# Sheet1.net
KiCad netlist of a schematic drawn in Altium Designer
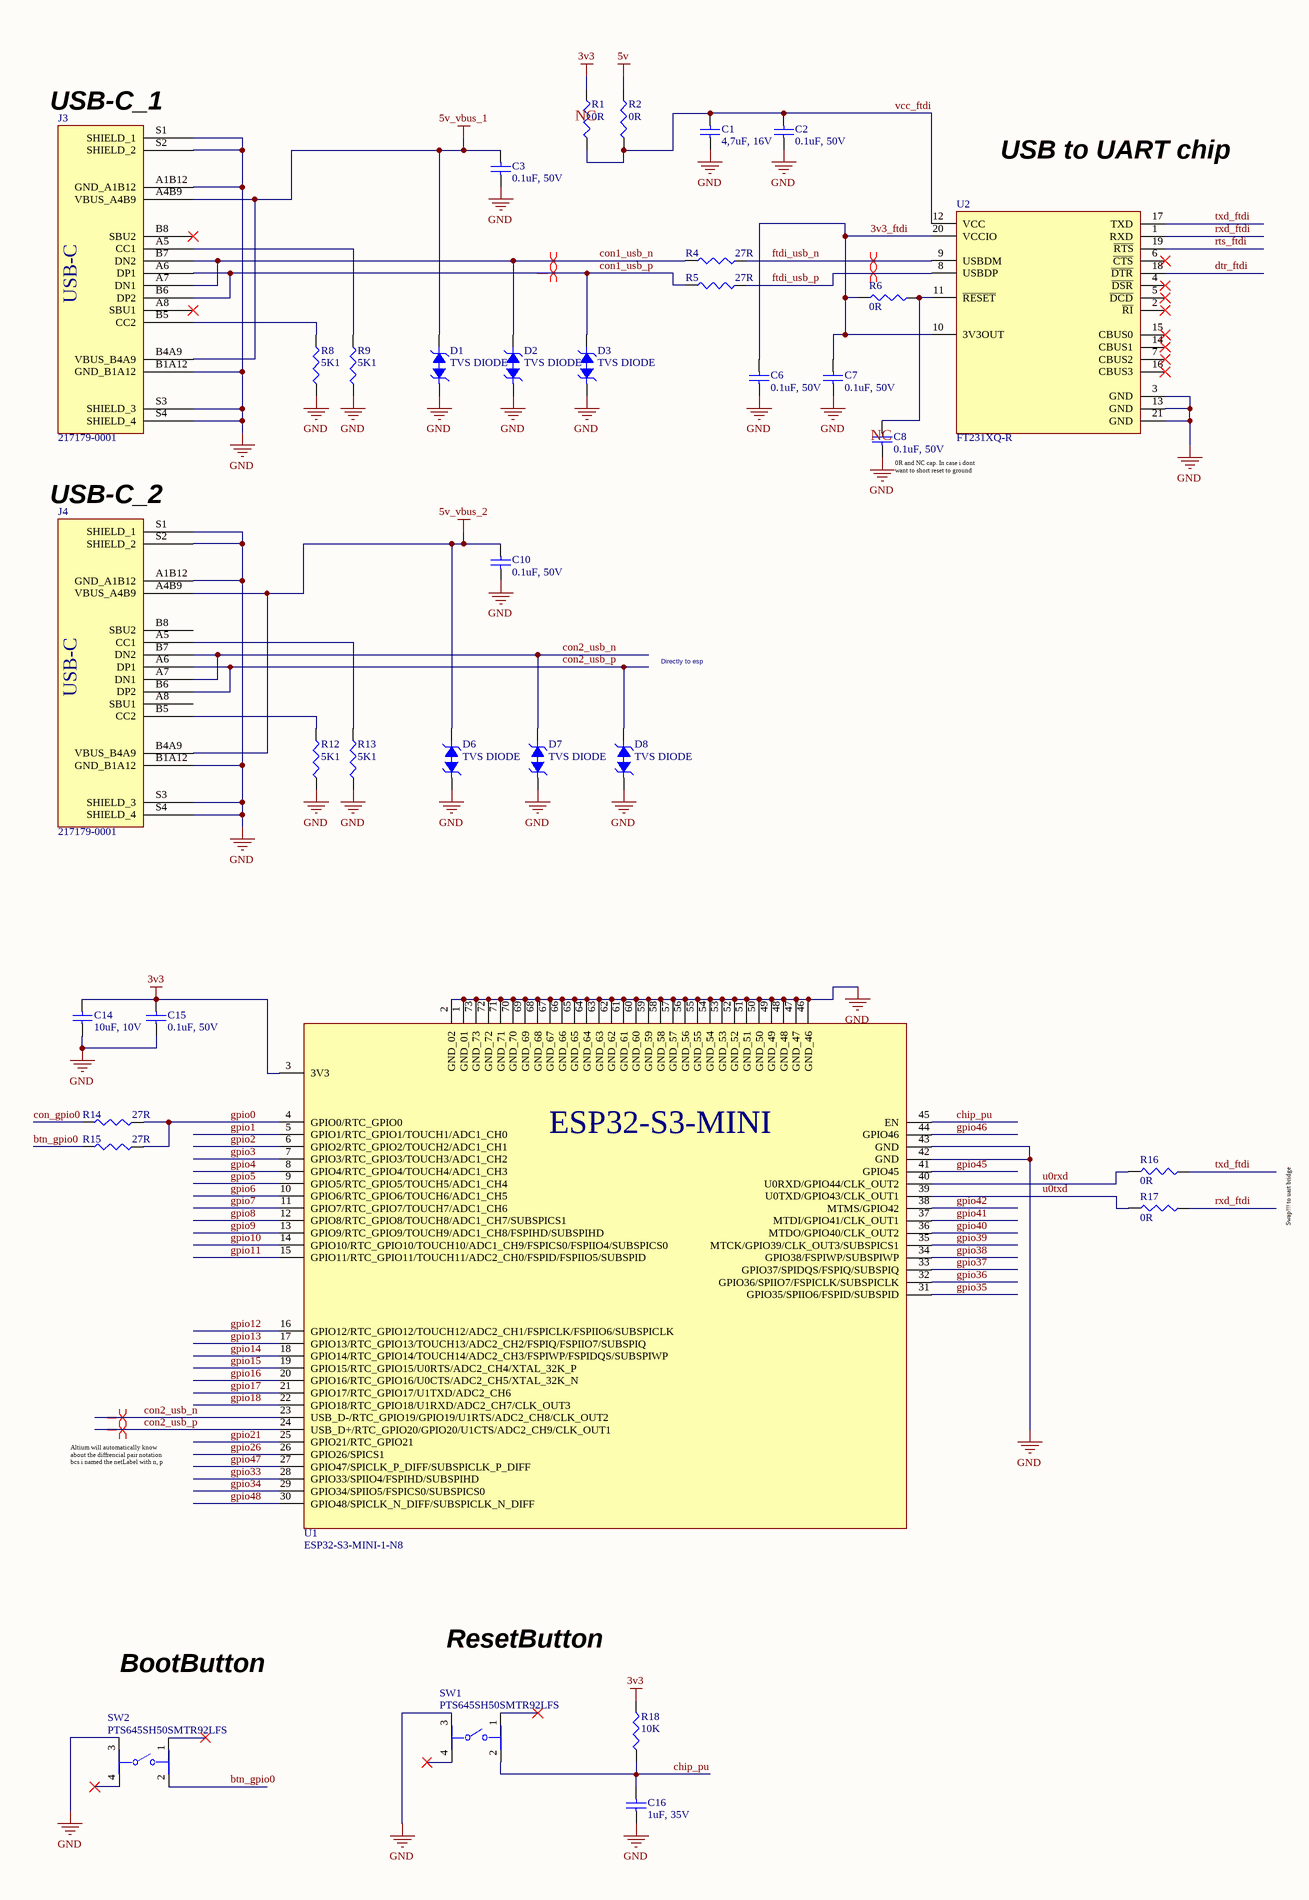
[diagram p0: Sheet1.SchDoc, left]
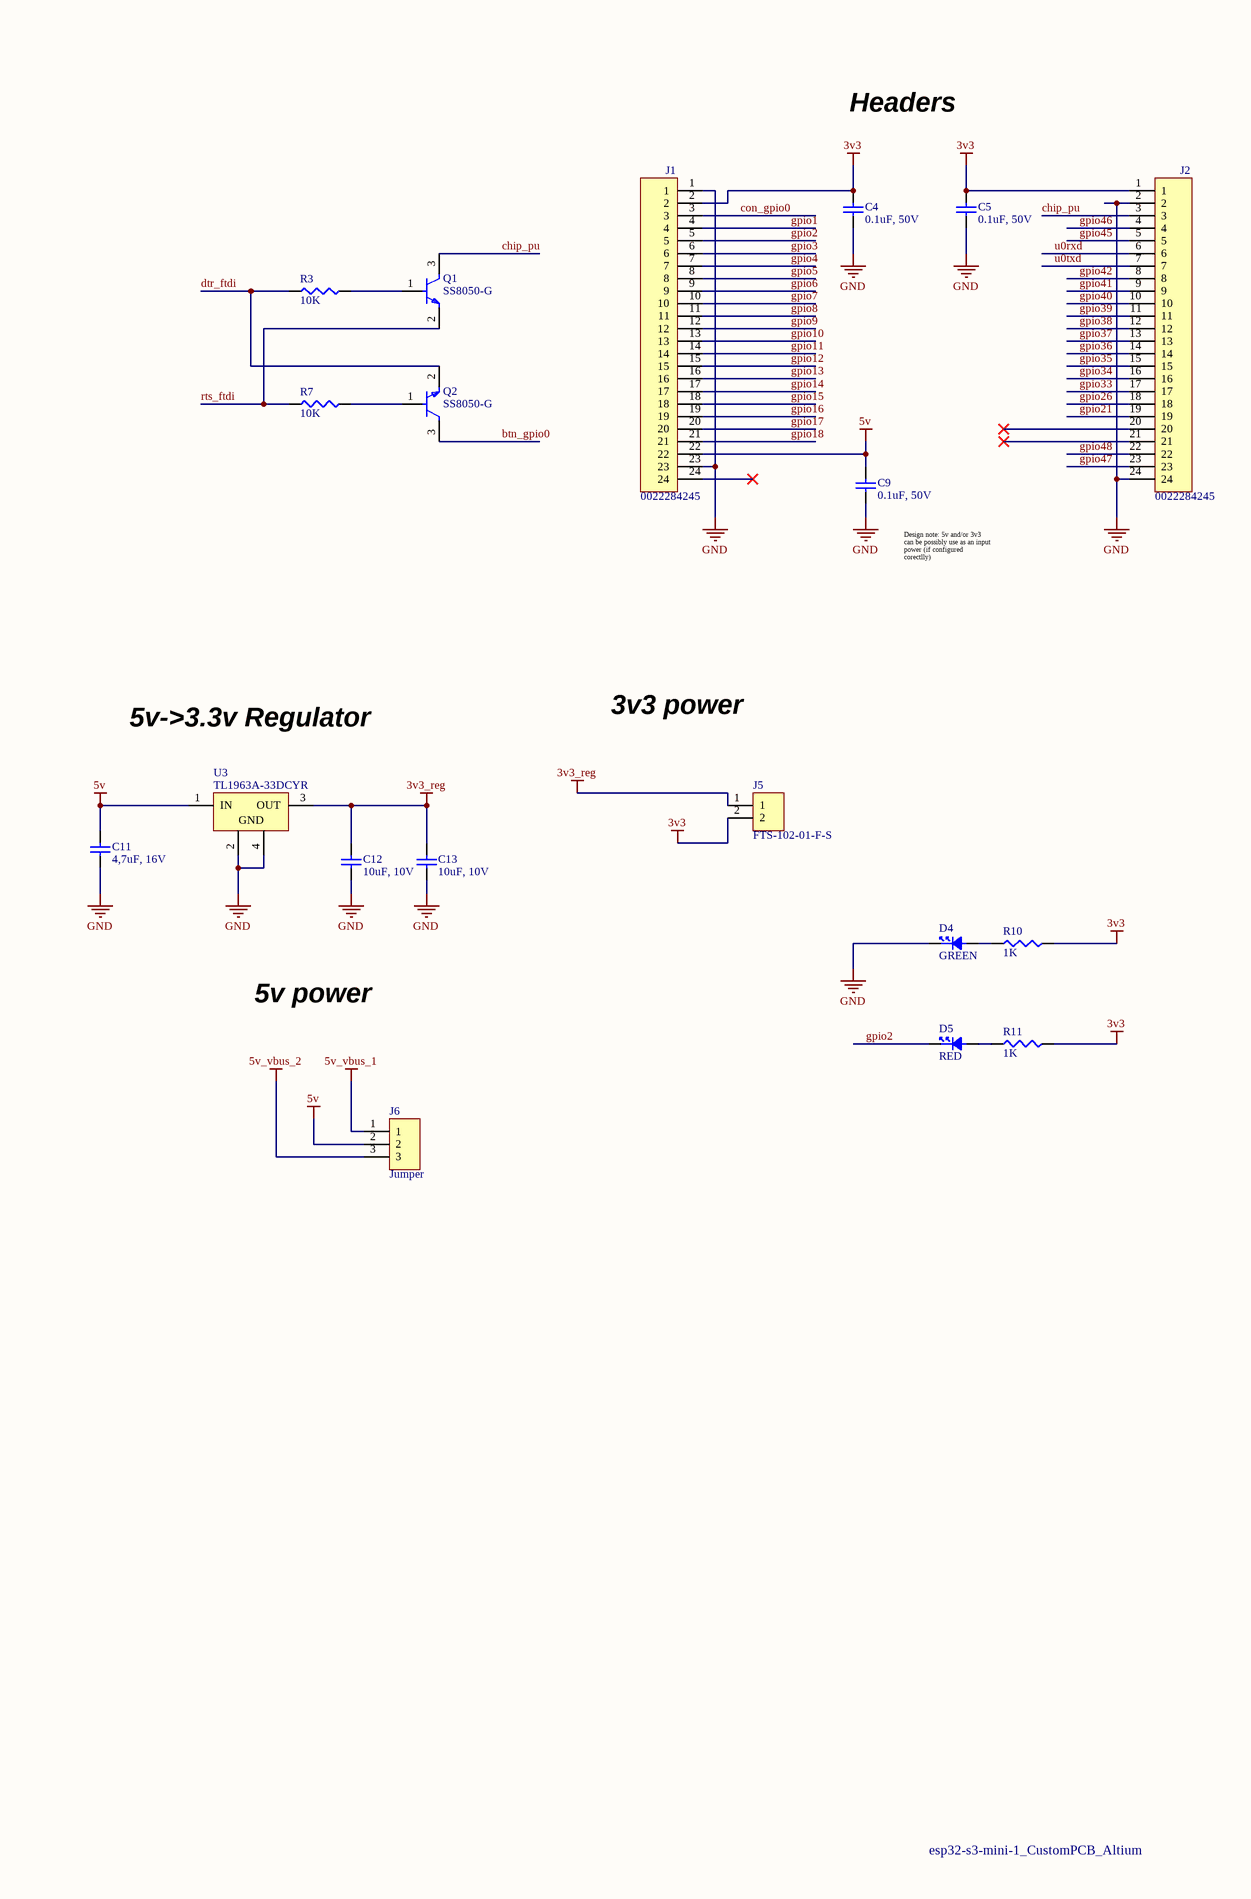
[diagram p1: Sheet1.SchDoc, right]

(export (version "E")
  (design (tool "Eeschema 10.0.6"))
  (components
    (comp (ref "C1")
      (value "4,7uF, 16V")
      (footprint "CAPC1005X55N")
      (description "CAP CER 4.7UF 16V X5R 0402")
      (fields
        (field (name "MANUFACTURER") "Samsung")
        (field (name "MANUFACTURER PART NUMBER") "CL05A475MO5NUNC")
      )
      (libsource (lib "Schlib1") (part "CL05A475MO5NUNC"))
    )
    (comp (ref "C2")
      (value "0.1uF, 50V")
      (footprint "CAPC1005X55N")
      (description "CAP CER 0.1UF 50V X7R 0402")
      (fields
        (field (name "MANUFACTURER") "Samsung")
        (field (name "MANUFACTURER PART NUMBER") "CL05B104KB54PNC")
      )
      (libsource (lib "Schlib1") (part "CL05B104KB54PNC"))
    )
    (comp (ref "C3")
      (value "0.1uF, 50V")
      (footprint "CAPC1005X55N")
      (description "CAP CER 0.1UF 50V X7R 0402")
      (fields
        (field (name "MANUFACTURER") "Samsung")
        (field (name "MANUFACTURER PART NUMBER") "CL05B104KB54PNC")
      )
      (libsource (lib "Schlib1") (part "CL05B104KB54PNC"))
    )
    (comp (ref "C4")
      (value "0.1uF, 50V")
      (footprint "CAPC1005X55N")
      (description "CAP CER 0.1UF 50V X7R 0402")
      (fields
        (field (name "MANUFACTURER") "Samsung")
        (field (name "MANUFACTURER PART NUMBER") "CL05B104KB54PNC")
      )
      (libsource (lib "Schlib1") (part "CL05B104KB54PNC"))
    )
    (comp (ref "C5")
      (value "0.1uF, 50V")
      (footprint "CAPC1005X55N")
      (description "CAP CER 0.1UF 50V X7R 0402")
      (fields
        (field (name "MANUFACTURER") "Samsung")
        (field (name "MANUFACTURER PART NUMBER") "CL05B104KB54PNC")
      )
      (libsource (lib "Schlib1") (part "CL05B104KB54PNC"))
    )
    (comp (ref "C6")
      (value "0.1uF, 50V")
      (footprint "CAPC1005X55N")
      (description "CAP CER 0.1UF 50V X7R 0402")
      (fields
        (field (name "MANUFACTURER") "Samsung")
        (field (name "MANUFACTURER PART NUMBER") "CL05B104KB54PNC")
      )
      (libsource (lib "Schlib1") (part "CL05B104KB54PNC"))
    )
    (comp (ref "C7")
      (value "0.1uF, 50V")
      (footprint "CAPC1005X55N")
      (description "CAP CER 0.1UF 50V X7R 0402")
      (fields
        (field (name "MANUFACTURER") "Samsung")
        (field (name "MANUFACTURER PART NUMBER") "CL05B104KB54PNC")
      )
      (libsource (lib "Schlib1") (part "CL05B104KB54PNC"))
    )
    (comp (ref "C8")
      (value "0.1uF, 50V")
      (footprint "CAPC1005X55N")
      (description "CAP CER 0.1UF 50V X7R 0402")
      (fields
        (field (name "MANUFACTURER") "Samsung")
        (field (name "MANUFACTURER PART NUMBER") "CL05B104KB54PNC")
      )
      (libsource (lib "Schlib1") (part "CL05B104KB54PNC"))
    )
    (comp (ref "C9")
      (value "0.1uF, 50V")
      (footprint "CAPC1005X55N")
      (description "CAP CER 0.1UF 50V X7R 0402")
      (fields
        (field (name "MANUFACTURER") "Samsung")
        (field (name "MANUFACTURER PART NUMBER") "CL05B104KB54PNC")
      )
      (libsource (lib "Schlib1") (part "CL05B104KB54PNC"))
    )
    (comp (ref "C10")
      (value "0.1uF, 50V")
      (footprint "CAPC1005X55N")
      (description "CAP CER 0.1UF 50V X7R 0402")
      (fields
        (field (name "MANUFACTURER") "Samsung")
        (field (name "MANUFACTURER PART NUMBER") "CL05B104KB54PNC")
      )
      (libsource (lib "Schlib1") (part "CL05B104KB54PNC"))
    )
    (comp (ref "C11")
      (value "4,7uF, 16V")
      (footprint "CAPC1005X55N")
      (description "CAP CER 4.7UF 16V X5R 0402")
      (fields
        (field (name "MANUFACTURER") "Samsung")
        (field (name "MANUFACTURER PART NUMBER") "CL05A475MO5NUNC")
      )
      (libsource (lib "Schlib1") (part "CL05A475MO5NUNC"))
    )
    (comp (ref "C12")
      (value "10uF, 10V")
      (footprint "CAPC1005X55N")
      (description "CAP CER 10UF 10V X5R 0402")
      (fields
        (field (name "MANUFACTURER") "Samsung")
        (field (name "MANUFACTURER PART NUMBER") "CL05A106MP8NUB8")
      )
      (libsource (lib "Schlib1") (part "CL05A106MP8NUB8"))
    )
    (comp (ref "C13")
      (value "10uF, 10V")
      (footprint "CAPC1005X55N")
      (description "CAP CER 10UF 10V X5R 0402")
      (fields
        (field (name "MANUFACTURER") "Samsung")
        (field (name "MANUFACTURER PART NUMBER") "CL05A106MP8NUB8")
      )
      (libsource (lib "Schlib1") (part "CL05A106MP8NUB8"))
    )
    (comp (ref "C14")
      (value "10uF, 10V")
      (footprint "CAPC1005X55N")
      (description "CAP CER 10UF 10V X5R 0402")
      (fields
        (field (name "MANUFACTURER") "Samsung")
        (field (name "MANUFACTURER PART NUMBER") "CL05A106MP8NUB8")
      )
      (libsource (lib "Schlib1") (part "CL05A106MP8NUB8"))
    )
    (comp (ref "C15")
      (value "0.1uF, 50V")
      (footprint "CAPC1005X55N")
      (description "CAP CER 0.1UF 50V X7R 0402")
      (fields
        (field (name "MANUFACTURER") "Samsung")
        (field (name "MANUFACTURER PART NUMBER") "CL05B104KB54PNC")
      )
      (libsource (lib "Schlib1") (part "CL05B104KB54PNC"))
    )
    (comp (ref "C16")
      (value "1uF, 35V")
      (footprint "CAPC1005X55N")
      (description "CAP CER 1UF 35V X5R 0402")
      (fields
        (field (name "MANUFACTURER") "Samsung")
        (field (name "MANUFACTURER PART NUMBER") "CL05A105KL5NRNC")
      )
      (libsource (lib "Schlib1") (part "CL05A105KL5NRNC"))
    )
    (comp (ref "D1")
      (value "TVS DIODE")
      (footprint "tvsDiode")
      (description "TVS DIODE 5.3VWM 12VC SOD882 - AQ3045-01ETG")
      (fields
        (field (name "MANUFACTURER") "Littelfuse")
        (field (name "MANUFACTURER PART NUMBER") "AQ3045-01ETG")
      )
      (libsource (lib "Schlib1") (part "TVS DIODE"))
    )
    (comp (ref "D2")
      (value "TVS DIODE")
      (footprint "tvsDiode")
      (description "TVS DIODE 5.3VWM 12VC SOD882 - AQ3045-01ETG")
      (fields
        (field (name "MANUFACTURER") "Littelfuse")
        (field (name "MANUFACTURER PART NUMBER") "AQ3045-01ETG")
      )
      (libsource (lib "Schlib1") (part "TVS DIODE"))
    )
    (comp (ref "D3")
      (value "TVS DIODE")
      (footprint "tvsDiode")
      (description "TVS DIODE 5.3VWM 12VC SOD882 - AQ3045-01ETG")
      (fields
        (field (name "MANUFACTURER") "Littelfuse")
        (field (name "MANUFACTURER PART NUMBER") "AQ3045-01ETG")
      )
      (libsource (lib "Schlib1") (part "TVS DIODE"))
    )
    (comp (ref "D4")
      (value "GREEN")
      (footprint "LED0402G")
      (description "LED YLW-GRN 0402 SMD")
      (fields
        (field (name "MANUFACTURER") "Vishay")
        (field (name "MANUFACTURER PART NUMBER") "VLMG1500-GS08")
      )
      (libsource (lib "Schlib1") (part "VLMG1500-GS08"))
    )
    (comp (ref "D5")
      (value "RED")
      (footprint "LED0402R")
      (description "LED RED 0402 SMD")
      (fields
        (field (name "MANUFACTURER") "Vishay")
        (field (name "MANUFACTURER PART NUMBER") "VLMS1500-GS08")
      )
      (libsource (lib "Schlib1") (part "VLMS1500-GS08"))
    )
    (comp (ref "D6")
      (value "TVS DIODE")
      (footprint "tvsDiode")
      (description "TVS DIODE 5.3VWM 12VC SOD882 - AQ3045-01ETG")
      (fields
        (field (name "MANUFACTURER") "Littelfuse")
        (field (name "MANUFACTURER PART NUMBER") "AQ3045-01ETG")
      )
      (libsource (lib "Schlib1") (part "TVS DIODE"))
    )
    (comp (ref "D7")
      (value "TVS DIODE")
      (footprint "tvsDiode")
      (description "TVS DIODE 5.3VWM 12VC SOD882 - AQ3045-01ETG")
      (fields
        (field (name "MANUFACTURER") "Littelfuse")
        (field (name "MANUFACTURER PART NUMBER") "AQ3045-01ETG")
      )
      (libsource (lib "Schlib1") (part "TVS DIODE"))
    )
    (comp (ref "D8")
      (value "TVS DIODE")
      (footprint "tvsDiode")
      (description "TVS DIODE 5.3VWM 12VC SOD882 - AQ3045-01ETG")
      (fields
        (field (name "MANUFACTURER") "Littelfuse")
        (field (name "MANUFACTURER PART NUMBER") "AQ3045-01ETG")
      )
      (libsource (lib "Schlib1") (part "TVS DIODE"))
    )
    (comp (ref "J1")
      (value "0022284245")
      (footprint "Header_1x24")
      (description "CONN HEADER VERT 24POS 2.54MM")
      (fields (field (name "MANUFACTURER") "Molex") (field (name "LCSC PART NUMBER") "C7145888"))
      (libsource (lib "") (part "0022284245_1"))
    )
    (comp (ref "J2")
      (value "0022284245")
      (footprint "Header_1x24")
      (description "CONN HEADER VERT 24POS 2.54MM")
      (fields (field (name "MANUFACTURER") "Molex") (field (name "LCSC PART NUMBER") "C7145888"))
      (libsource (lib "Schlib1") (part "0022284245"))
    )
    (comp (ref "J3")
      (value "217179-0001")
      (footprint "FP-2171790001-MFG")
      (description "CONN RCP USB2.0 TYP C 24P SMD RA")
      (fields (field (name "MANUFACTURER") "Molex") (field (name "LCSC PART NUMBER") "C3197684"))
      (libsource (lib "Schlib1") (part "217179-0001"))
    )
    (comp (ref "J4")
      (value "217179-0001")
      (footprint "FP-2171790001-MFG")
      (description "CONN RCP USB2.0 TYP C 24P SMD RA")
      (fields (field (name "MANUFACTURER") "Molex") (field (name "LCSC PART NUMBER") "C3197684"))
      (libsource (lib "Schlib1") (part "217179-0001"))
    )
    (comp (ref "J5")
      (value "FTS-102-01-F-S")
      (footprint "Header_1X2")
      (description "CONN HEADER VERT 2POS 1.27MM")
      (fields (field (name "MANUFACTURER") "Samtec") (field (name "LCSC PART NUMBER") "C6045317"))
      (libsource (lib "Schlib1") (part "FTS-102-01-F-S"))
    )
    (comp (ref "J6")
      (value "Jumper")
      (footprint "Header_3x1")
      (description "CONN HEADER VERT 3POS 1.27MM")
      (fields
        (field (name "MANUFACTURER") "Samtec")
        (field (name "MANUFACTURER PART NUMBER") "FTS-103-01-F-S")
      )
      (libsource (lib "Schlib1") (part "FTS-103-01-F-S."))
    )
    (comp (ref "Q1")
      (value "SS8050-G")
      (footprint "FP-SS8050-G-IPC_B")
      (description "TRANS NPN 25V 1.5A SOT23-3")
      (fields (field (name "MANUFACTURER") "Comchip") (field (name "LCSC PART NUMBER") "C164886"))
      (libsource (lib "Schlib1") (part "SS8050-G"))
    )
    (comp (ref "Q2")
      (value "SS8050-G")
      (footprint "FP-SS8050-G-IPC_B")
      (description "TRANS NPN 25V 1.5A SOT23-3")
      (fields (field (name "MANUFACTURER") "Comchip") (field (name "LCSC PART NUMBER") "C164886"))
      (libsource (lib "Schlib1") (part "SS8050-G"))
    )
    (comp (ref "R1")
      (value "0R")
      (footprint "RESC1005X37N")
      (description "RES 0 OHM JUMPER 1/16W 0402")
      (fields
        (field (name "MANUFACTURER") "Yageo")
        (field (name "MANUFACTURER PART NUMBER") "RC0402JR-070RL")
      )
      (libsource (lib "Schlib1") (part "RC0402JR-070RL"))
    )
    (comp (ref "R2")
      (value "0R")
      (footprint "RESC1005X37N")
      (description "RES 0 OHM JUMPER 1/16W 0402")
      (fields
        (field (name "MANUFACTURER") "Yageo")
        (field (name "MANUFACTURER PART NUMBER") "RC0402JR-070RL")
      )
      (libsource (lib "Schlib1") (part "RC0402JR-070RL"))
    )
    (comp (ref "R3")
      (value "10K")
      (footprint "RESC1005X37N")
      (description "RES SMD 10K OHM 1% 1/16W 0402")
      (fields
        (field (name "MANUFACTURER") "Yageo")
        (field (name "MANUFACTURER PART NUMBER") "AC0402FR-0710KL")
      )
      (libsource (lib "Schlib1") (part "AC0402FR-0710KL"))
    )
    (comp (ref "R4")
      (value "27R")
      (footprint "RESC1005X37N")
      (description "RES 27 OHM 1% 1/16W 0402")
      (fields
        (field (name "MANUFACTURER") "Yageo")
        (field (name "MANUFACTURER PART NUMBER") "RC0402FR-0727RL")
      )
      (libsource (lib "Schlib1") (part "RC0402FR-0727RL"))
    )
    (comp (ref "R5")
      (value "27R")
      (footprint "RESC1005X37N")
      (description "RES 27 OHM 1% 1/16W 0402")
      (fields
        (field (name "MANUFACTURER") "Yageo")
        (field (name "MANUFACTURER PART NUMBER") "RC0402FR-0727RL")
      )
      (libsource (lib "Schlib1") (part "RC0402FR-0727RL"))
    )
    (comp (ref "R6")
      (value "0R")
      (footprint "RESC1005X37N")
      (description "RES 0 OHM JUMPER 1/16W 0402")
      (fields
        (field (name "MANUFACTURER") "Yageo")
        (field (name "MANUFACTURER PART NUMBER") "RC0402JR-070RL")
      )
      (libsource (lib "Schlib1") (part "RC0402JR-070RL"))
    )
    (comp (ref "R7")
      (value "10K")
      (footprint "RESC1005X37N")
      (description "RES SMD 10K OHM 1% 1/16W 0402")
      (fields
        (field (name "MANUFACTURER") "Yageo")
        (field (name "MANUFACTURER PART NUMBER") "AC0402FR-0710KL")
      )
      (libsource (lib "Schlib1") (part "AC0402FR-0710KL"))
    )
    (comp (ref "R8")
      (value "5K1")
      (footprint "RESC1005X37N")
      (description "RES SMD 5.1K OHM 1% 1/16W 0402")
      (fields
        (field (name "MANUFACTURER") "Yageo")
        (field (name "MANUFACTURER PART NUMBER") "AC0402FR-075K1L")
      )
      (libsource (lib "Schlib1") (part "AC0402FR-075K1L"))
    )
    (comp (ref "R9")
      (value "5K1")
      (footprint "RESC1005X37N")
      (description "RES SMD 5.1K OHM 1% 1/16W 0402")
      (fields
        (field (name "MANUFACTURER") "Yageo")
        (field (name "MANUFACTURER PART NUMBER") "AC0402FR-075K1L")
      )
      (libsource (lib "*") (part "AC0402FR-075K1L"))
    )
    (comp (ref "R10")
      (value "1K")
      (footprint "RESC1005X37N")
      (description "RES 1K OHM 1% 1/16W 0402")
      (fields
        (field (name "MANUFACTURER") "Yageo")
        (field (name "MANUFACTURER PART NUMBER") "RC0402FR-071KL")
      )
      (libsource (lib "Schlib1") (part "RC0402FR-071KL"))
    )
    (comp (ref "R11")
      (value "1K")
      (footprint "RESC1005X37N")
      (description "RES 1K OHM 1% 1/16W 0402")
      (fields
        (field (name "MANUFACTURER") "Yageo")
        (field (name "MANUFACTURER PART NUMBER") "RC0402FR-071KL")
      )
      (libsource (lib "Schlib1") (part "RC0402FR-071KL"))
    )
    (comp (ref "R12")
      (value "5K1")
      (footprint "RESC1005X37N")
      (description "RES SMD 5.1K OHM 1% 1/16W 0402")
      (fields
        (field (name "MANUFACTURER") "Yageo")
        (field (name "MANUFACTURER PART NUMBER") "AC0402FR-075K1L")
      )
      (libsource (lib "Schlib1") (part "AC0402FR-075K1L"))
    )
    (comp (ref "R13")
      (value "5K1")
      (footprint "RESC1005X37N")
      (description "RES SMD 5.1K OHM 1% 1/16W 0402")
      (fields
        (field (name "MANUFACTURER") "Yageo")
        (field (name "MANUFACTURER PART NUMBER") "AC0402FR-075K1L")
      )
      (libsource (lib "*") (part "AC0402FR-075K1L"))
    )
    (comp (ref "R14")
      (value "27R")
      (footprint "RESC1005X37N")
      (description "RES 27 OHM 1% 1/16W 0402")
      (fields
        (field (name "MANUFACTURER") "Yageo")
        (field (name "MANUFACTURER PART NUMBER") "RC0402FR-0727RL")
      )
      (libsource (lib "Schlib1") (part "RC0402FR-0727RL"))
    )
    (comp (ref "R15")
      (value "27R")
      (footprint "RESC1005X37N")
      (description "RES 27 OHM 1% 1/16W 0402")
      (fields
        (field (name "MANUFACTURER") "Yageo")
        (field (name "MANUFACTURER PART NUMBER") "RC0402FR-0727RL")
      )
      (libsource (lib "Schlib1") (part "RC0402FR-0727RL"))
    )
    (comp (ref "R16")
      (value "0R")
      (footprint "RESC1005X37N")
      (description "RES 0 OHM JUMPER 1/16W 0402")
      (fields
        (field (name "MANUFACTURER") "Yageo")
        (field (name "MANUFACTURER PART NUMBER") "RC0402JR-070RL")
      )
      (libsource (lib "Schlib1") (part "RC0402JR-070RL"))
    )
    (comp (ref "R17")
      (value "0R")
      (footprint "RESC1005X37N")
      (description "RES 0 OHM JUMPER 1/16W 0402")
      (fields
        (field (name "MANUFACTURER") "Yageo")
        (field (name "MANUFACTURER PART NUMBER") "RC0402JR-070RL")
      )
      (libsource (lib "Schlib1") (part "RC0402JR-070RL"))
    )
    (comp (ref "R18")
      (value "10K")
      (footprint "RESC1005X37N")
      (description "RES SMD 10K OHM 1% 1/16W 0402")
      (fields
        (field (name "MANUFACTURER") "Yageo")
        (field (name "MANUFACTURER PART NUMBER") "AC0402FR-0710KL")
      )
      (libsource (lib "Schlib1") (part "AC0402FR-0710KL"))
    )
    (comp (ref "SW1")
      (value "PTS645SH50SMTR92LFS")
      (footprint "FP-PTS645SH50SMTR92LFS-MFG")
      (description "SWITCH TACTILE SPST-NO 0.05A 12V")
      (fields (field (name "MANUFACTURER") "ITT C&K") (field (name "LCSC PART NUMBER") "C221869"))
      (libsource (lib "Schlib1") (part "PTS645SH50SMTR92LFS"))
    )
    (comp (ref "SW2")
      (value "PTS645SH50SMTR92LFS")
      (footprint "FP-PTS645SH50SMTR92LFS-MFG")
      (description "SWITCH TACTILE SPST-NO 0.05A 12V")
      (fields (field (name "MANUFACTURER") "ITT C&K") (field (name "LCSC PART NUMBER") "C221869"))
      (libsource (lib "Schlib1") (part "PTS645SH50SMTR92LFS"))
    )
    (comp (ref "U1")
      (value "ESP32-S3-MINI-1-N8")
      (footprint "XCVR_ESP32-S3-MINI-1-N8")
      (description "SMD Module, ESP32-S3FN8, 8 mb Sp")
      (fields (field (name "MANUFACTURER") "Espressif Systems") (field (name "LCSC PART NUMBER") "C2913206"))
      (libsource (lib "Schlib1") (part "ESP32-S3-MINI-1-N8"))
    )
    (comp (ref "U2")
      (value "FT231XQ-R")
      (footprint "FP-QFN-20-IPC_B")
      (description "IC USB SERIAL FULL UART 20QFN")
      (fields (field (name "MANUFACTURER") "FTDI") (field (name "LCSC PART NUMBER") "C132159"))
      (libsource (lib "Schlib1") (part "FT231XQ-R"))
    )
    (comp (ref "U3")
      (value "TL1963A-33DCYR")
      (footprint "DCY0004A_N")
      (description "IC REG LINEAR 3.3V 1.5A SOT223-4")
      (fields (field (name "MANUFACTURER") "Texas Instruments") (field (name "LCSC PART NUMBER") "C181262"))
      (libsource (lib "Schlib1") (part "TL1963A-33DCYR"))
    )
  )
  (nets
    (net (code "1") (name "/3v3_ftdi") (class "Default")
      (node (ref "C6") (pin "2") (pinfunction "2_2") (pintype "passive"))
      (node (ref "C7") (pin "2") (pinfunction "2_2") (pintype "passive"))
      (node (ref "R6") (pin "2") (pinfunction "2_2") (pintype "passive"))
      (node (ref "U2") (pin "10") (pinfunction "3V3OUT_10") (pintype "passive"))
      (node (ref "U2") (pin "20") (pinfunction "VCCIO_20") (pintype "passive"))
    )
    (net (code "2") (name "/btn_gpio0") (class "Default")
      (node (ref "Q2") (pin "3") (pinfunction "C_3") (pintype "passive"))
      (node (ref "R15") (pin "1") (pinfunction "1_1") (pintype "passive"))
      (node (ref "SW2") (pin "2") (pinfunction "2_2") (pintype "passive"))
    )
    (net (code "3") (name "/chip_pu") (class "Default")
      (node (ref "C16") (pin "2") (pinfunction "2_2") (pintype "passive"))
      (node (ref "J2") (pin "3") (pinfunction "3_3") (pintype "passive"))
      (node (ref "Q1") (pin "3") (pinfunction "C_3") (pintype "passive"))
      (node (ref "R18") (pin "1") (pinfunction "1_1") (pintype "passive"))
      (node (ref "SW1") (pin "2") (pinfunction "2_2") (pintype "passive"))
      (node (ref "U1") (pin "45") (pinfunction "EN_45") (pintype "passive"))
    )
    (net (code "4") (name "/con1_usb_n") (class "Default")
      (node (ref "D2") (pin "2") (pinfunction "2_2") (pintype "passive"))
      (node (ref "J3") (pin "A7") (pinfunction "DN1_A7") (pintype "passive"))
      (node (ref "J3") (pin "B7") (pinfunction "DN2_B7") (pintype "passive"))
      (node (ref "R4") (pin "1") (pinfunction "1_1") (pintype "passive"))
    )
    (net (code "5") (name "/con1_usb_p") (class "Default")
      (node (ref "D3") (pin "2") (pinfunction "2_2") (pintype "passive"))
      (node (ref "J3") (pin "A6") (pinfunction "DP1_A6") (pintype "passive"))
      (node (ref "J3") (pin "B6") (pinfunction "DP2_B6") (pintype "passive"))
      (node (ref "R5") (pin "1") (pinfunction "1_1") (pintype "passive"))
    )
    (net (code "6") (name "/con2_usb_n") (class "Default")
      (node (ref "D7") (pin "2") (pinfunction "2_2") (pintype "passive"))
      (node (ref "J4") (pin "A7") (pinfunction "DN1_A7") (pintype "passive"))
      (node (ref "J4") (pin "B7") (pinfunction "DN2_B7") (pintype "passive"))
      (node (ref "U1") (pin "23") (pinfunction "USB_D-/RTC_GPIO19/GPIO19/U1RTS/ADC2_CH8/CLK_OUT2_23") (pintype "passive"))
    )
    (net (code "7") (name "/con2_usb_p") (class "Default")
      (node (ref "D8") (pin "2") (pinfunction "2_2") (pintype "passive"))
      (node (ref "J4") (pin "A6") (pinfunction "DP1_A6") (pintype "passive"))
      (node (ref "J4") (pin "B6") (pinfunction "DP2_B6") (pintype "passive"))
      (node (ref "U1") (pin "24") (pinfunction "USB_D+/RTC_GPIO20/GPIO20/U1CTS/ADC2_CH9/CLK_OUT1_24") (pintype "passive"))
    )
    (net (code "8") (name "/con_gpio0") (class "Default")
      (node (ref "J1") (pin "3") (pinfunction "3_3") (pintype "passive"))
      (node (ref "R14") (pin "1") (pinfunction "1_1") (pintype "passive"))
    )
    (net (code "9") (name "/dtr_ftdi") (class "Default")
      (node (ref "Q2") (pin "2") (pinfunction "E_2") (pintype "passive"))
      (node (ref "R3") (pin "1") (pinfunction "1_1") (pintype "passive"))
      (node (ref "U2") (pin "18") (pinfunction "~{DTR}_18") (pintype "passive"))
    )
    (net (code "10") (name "/ftdi_usb_n") (class "Default")
      (node (ref "R4") (pin "2") (pinfunction "2_2") (pintype "passive"))
      (node (ref "U2") (pin "9") (pinfunction "USBDM_9") (pintype "passive"))
    )
    (net (code "11") (name "/ftdi_usb_p") (class "Default")
      (node (ref "R5") (pin "2") (pinfunction "2_2") (pintype "passive"))
      (node (ref "U2") (pin "8") (pinfunction "USBDP_8") (pintype "passive"))
    )
    (net (code "12") (name "/gpio0") (class "Default")
      (node (ref "R14") (pin "2") (pinfunction "2_2") (pintype "passive"))
      (node (ref "R15") (pin "2") (pinfunction "2_2") (pintype "passive"))
      (node (ref "U1") (pin "4") (pinfunction "GPIO0/RTC_GPIO0_4") (pintype "passive"))
    )
    (net (code "13") (name "/gpio1") (class "Default")
      (node (ref "J1") (pin "4") (pinfunction "4_4") (pintype "passive"))
      (node (ref "U1") (pin "5") (pinfunction "GPIO1/RTC_GPIO1/TOUCH1/ADC1_CH0_5") (pintype "passive"))
    )
    (net (code "14") (name "/gpio2") (class "Default")
      (node (ref "D5") (pin "1") (pinfunction "1_1") (pintype "passive"))
      (node (ref "J1") (pin "5") (pinfunction "5_5") (pintype "passive"))
      (node (ref "U1") (pin "6") (pinfunction "GPIO2/RTC_GPIO2/TOUCH2/ADC1_CH1_6") (pintype "passive"))
    )
    (net (code "15") (name "/gpio3") (class "Default")
      (node (ref "J1") (pin "6") (pinfunction "6_6") (pintype "passive"))
      (node (ref "U1") (pin "7") (pinfunction "GPIO3/RTC_GPIO3/TOUCH3/ADC1_CH2_7") (pintype "passive"))
    )
    (net (code "16") (name "/gpio4") (class "Default")
      (node (ref "J1") (pin "7") (pinfunction "7_7") (pintype "passive"))
      (node (ref "U1") (pin "8") (pinfunction "GPIO4/RTC_GPIO4/TOUCH4/ADC1_CH3_8") (pintype "passive"))
    )
    (net (code "17") (name "/gpio5") (class "Default")
      (node (ref "J1") (pin "8") (pinfunction "8_8") (pintype "passive"))
      (node (ref "U1") (pin "9") (pinfunction "GPIO5/RTC_GPIO5/TOUCH5/ADC1_CH4_9") (pintype "passive"))
    )
    (net (code "18") (name "/gpio6") (class "Default")
      (node (ref "J1") (pin "9") (pinfunction "9_9") (pintype "passive"))
      (node (ref "U1") (pin "10") (pinfunction "GPIO6/RTC_GPIO6/TOUCH6/ADC1_CH5_10") (pintype "passive"))
    )
    (net (code "19") (name "/gpio7") (class "Default")
      (node (ref "J1") (pin "10") (pinfunction "10_10") (pintype "passive"))
      (node (ref "U1") (pin "11") (pinfunction "GPIO7/RTC_GPIO7/TOUCH7/ADC1_CH6_11") (pintype "passive"))
    )
    (net (code "20") (name "/gpio8") (class "Default")
      (node (ref "J1") (pin "11") (pinfunction "11_11") (pintype "passive"))
      (node (ref "U1") (pin "12") (pinfunction "GPIO8/RTC_GPIO8/TOUCH8/ADC1_CH7/SUBSPICS1_12") (pintype "passive"))
    )
    (net (code "21") (name "/gpio9") (class "Default")
      (node (ref "J1") (pin "12") (pinfunction "12_12") (pintype "passive"))
      (node (ref "U1") (pin "13") (pinfunction "GPIO9/RTC_GPIO9/TOUCH9/ADC1_CH8/FSPIHD/SUBSPIHD_13") (pintype "passive"))
    )
    (net (code "22") (name "/gpio10") (class "Default")
      (node (ref "J1") (pin "13") (pinfunction "13_13") (pintype "passive"))
      (node (ref "U1") (pin "14") (pinfunction "GPIO10/RTC_GPIO10/TOUCH10/ADC1_CH9/FSPICS0/FSPIIO4/SUBSPICS0_14") (pintype "passive"))
    )
    (net (code "23") (name "/gpio11") (class "Default")
      (node (ref "J1") (pin "14") (pinfunction "14_14") (pintype "passive"))
      (node (ref "U1") (pin "15") (pinfunction "GPIO11/RTC_GPIO11/TOUCH11/ADC2_CH0/FSPID/FSPIIO5/SUBSPID_15") (pintype "passive"))
    )
    (net (code "24") (name "/gpio12") (class "Default")
      (node (ref "J1") (pin "15") (pinfunction "15_15") (pintype "passive"))
      (node (ref "U1") (pin "16") (pinfunction "GPIO12/RTC_GPIO12/TOUCH12/ADC2_CH1/FSPICLK/FSPIIO6/SUBSPICLK_16") (pintype "passive"))
    )
    (net (code "25") (name "/gpio13") (class "Default")
      (node (ref "J1") (pin "16") (pinfunction "16_16") (pintype "passive"))
      (node (ref "U1") (pin "17") (pinfunction "GPIO13/RTC_GPIO13/TOUCH13/ADC2_CH2/FSPIQ/FSPIIO7/SUBSPIQ_17") (pintype "passive"))
    )
    (net (code "26") (name "/gpio14") (class "Default")
      (node (ref "J1") (pin "17") (pinfunction "17_17") (pintype "passive"))
      (node (ref "U1") (pin "18") (pinfunction "GPIO14/RTC_GPIO14/TOUCH14/ADC2_CH3/FSPIWP/FSPIDQS/SUBSPIWP_18") (pintype "passive"))
    )
    (net (code "27") (name "/gpio15") (class "Default")
      (node (ref "J1") (pin "18") (pinfunction "18_18") (pintype "passive"))
      (node (ref "U1") (pin "19") (pinfunction "GPIO15/RTC_GPIO15/U0RTS/ADC2_CH4/XTAL_32K_P_19") (pintype "passive"))
    )
    (net (code "28") (name "/gpio16") (class "Default")
      (node (ref "J1") (pin "19") (pinfunction "19_19") (pintype "passive"))
      (node (ref "U1") (pin "20") (pinfunction "GPIO16/RTC_GPIO16/U0CTS/ADC2_CH5/XTAL_32K_N_20") (pintype "passive"))
    )
    (net (code "29") (name "/gpio17") (class "Default")
      (node (ref "J1") (pin "20") (pinfunction "20_20") (pintype "passive"))
      (node (ref "U1") (pin "21") (pinfunction "GPIO17/RTC_GPIO17/U1TXD/ADC2_CH6_21") (pintype "passive"))
    )
    (net (code "30") (name "/gpio18") (class "Default")
      (node (ref "J1") (pin "21") (pinfunction "21_21") (pintype "passive"))
      (node (ref "U1") (pin "22") (pinfunction "GPIO18/RTC_GPIO18/U1RXD/ADC2_CH7/CLK_OUT3_22") (pintype "passive"))
    )
    (net (code "31") (name "/gpio21") (class "Default")
      (node (ref "J2") (pin "19") (pinfunction "19_19") (pintype "passive"))
      (node (ref "U1") (pin "25") (pinfunction "GPIO21/RTC_GPIO21_25") (pintype "passive"))
    )
    (net (code "32") (name "/gpio26") (class "Default")
      (node (ref "J2") (pin "18") (pinfunction "18_18") (pintype "passive"))
      (node (ref "U1") (pin "26") (pinfunction "GPIO26/SPICS1_26") (pintype "passive"))
    )
    (net (code "33") (name "/gpio33") (class "Default")
      (node (ref "J2") (pin "17") (pinfunction "17_17") (pintype "passive"))
      (node (ref "U1") (pin "28") (pinfunction "GPIO33/SPIIO4/FSPIHD/SUBSPIHD_28") (pintype "passive"))
    )
    (net (code "34") (name "/gpio34") (class "Default")
      (node (ref "J2") (pin "16") (pinfunction "16_16") (pintype "passive"))
      (node (ref "U1") (pin "29") (pinfunction "GPIO34/SPIIO5/FSPICS0/SUBSPICS0_29") (pintype "passive"))
    )
    (net (code "35") (name "/gpio35") (class "Default")
      (node (ref "J2") (pin "15") (pinfunction "15_15") (pintype "passive"))
      (node (ref "U1") (pin "31") (pinfunction "GPIO35/SPIIO6/FSPID/SUBSPID_31") (pintype "passive"))
    )
    (net (code "36") (name "/gpio36") (class "Default")
      (node (ref "J2") (pin "14") (pinfunction "14_14") (pintype "passive"))
      (node (ref "U1") (pin "32") (pinfunction "GPIO36/SPIIO7/FSPICLK/SUBSPICLK_32") (pintype "passive"))
    )
    (net (code "37") (name "/gpio37") (class "Default")
      (node (ref "J2") (pin "13") (pinfunction "13_13") (pintype "passive"))
      (node (ref "U1") (pin "33") (pinfunction "GPIO37/SPIDQS/FSPIQ/SUBSPIQ_33") (pintype "passive"))
    )
    (net (code "38") (name "/gpio38") (class "Default")
      (node (ref "J2") (pin "12") (pinfunction "12_12") (pintype "passive"))
      (node (ref "U1") (pin "34") (pinfunction "GPIO38/FSPIWP/SUBSPIWP_34") (pintype "passive"))
    )
    (net (code "39") (name "/gpio39") (class "Default")
      (node (ref "J2") (pin "11") (pinfunction "11_11") (pintype "passive"))
      (node (ref "U1") (pin "35") (pinfunction "MTCK/GPIO39/CLK_OUT3/SUBSPICS1_35") (pintype "passive"))
    )
    (net (code "40") (name "/gpio40") (class "Default")
      (node (ref "J2") (pin "10") (pinfunction "10_10") (pintype "passive"))
      (node (ref "U1") (pin "36") (pinfunction "MTDO/GPIO40/CLK_OUT2_36") (pintype "passive"))
    )
    (net (code "41") (name "/gpio41") (class "Default")
      (node (ref "J2") (pin "9") (pinfunction "9_9") (pintype "passive"))
      (node (ref "U1") (pin "37") (pinfunction "MTDI/GPIO41/CLK_OUT1_37") (pintype "passive"))
    )
    (net (code "42") (name "/gpio42") (class "Default")
      (node (ref "J2") (pin "8") (pinfunction "8_8") (pintype "passive"))
      (node (ref "U1") (pin "38") (pinfunction "MTMS/GPIO42_38") (pintype "passive"))
    )
    (net (code "43") (name "/gpio45") (class "Default")
      (node (ref "J2") (pin "5") (pinfunction "5_5") (pintype "passive"))
      (node (ref "U1") (pin "41") (pinfunction "GPIO45_41") (pintype "passive"))
    )
    (net (code "44") (name "/gpio46") (class "Default")
      (node (ref "J2") (pin "4") (pinfunction "4_4") (pintype "passive"))
      (node (ref "U1") (pin "44") (pinfunction "GPIO46_44") (pintype "passive"))
    )
    (net (code "45") (name "/gpio47") (class "Default")
      (node (ref "J2") (pin "23") (pinfunction "23_23") (pintype "passive"))
      (node (ref "U1") (pin "27") (pinfunction "GPIO47/SPICLK_P_DIFF/SUBSPICLK_P_DIFF_27") (pintype "passive"))
    )
    (net (code "46") (name "/gpio48") (class "Default")
      (node (ref "J2") (pin "22") (pinfunction "22_22") (pintype "passive"))
      (node (ref "U1") (pin "30") (pinfunction "GPIO48/SPICLK_N_DIFF/SUBSPICLK_N_DIFF_30") (pintype "passive"))
    )
    (net (code "47") (name "/rts_ftdi") (class "Default")
      (node (ref "Q1") (pin "2") (pinfunction "E_2") (pintype "passive"))
      (node (ref "R7") (pin "1") (pinfunction "1_1") (pintype "passive"))
      (node (ref "U2") (pin "19") (pinfunction "~{RTS}_19") (pintype "passive"))
    )
    (net (code "48") (name "/rxd_ftdi") (class "Default")
      (node (ref "R17") (pin "1") (pinfunction "1_1") (pintype "passive"))
      (node (ref "U2") (pin "1") (pinfunction "RXD_1") (pintype "passive"))
    )
    (net (code "49") (name "/txd_ftdi") (class "Default")
      (node (ref "R16") (pin "1") (pinfunction "1_1") (pintype "passive"))
      (node (ref "U2") (pin "17") (pinfunction "TXD_17") (pintype "passive"))
    )
    (net (code "50") (name "/u0rxd") (class "Default")
      (node (ref "J2") (pin "6") (pinfunction "6_6") (pintype "passive"))
      (node (ref "R16") (pin "2") (pinfunction "2_2") (pintype "passive"))
      (node (ref "U1") (pin "40") (pinfunction "U0RXD/GPIO44/CLK_OUT2_40") (pintype "passive"))
    )
    (net (code "51") (name "/u0txd") (class "Default")
      (node (ref "J2") (pin "7") (pinfunction "7_7") (pintype "passive"))
      (node (ref "R17") (pin "2") (pinfunction "2_2") (pintype "passive"))
      (node (ref "U1") (pin "39") (pinfunction "U0TXD/GPIO43/CLK_OUT1_39") (pintype "passive"))
    )
    (net (code "52") (name "/vcc_ftdi") (class "Default")
      (node (ref "C1") (pin "2") (pinfunction "2_2") (pintype "passive"))
      (node (ref "C2") (pin "2") (pinfunction "2_2") (pintype "passive"))
      (node (ref "R1") (pin "1") (pinfunction "1_1") (pintype "passive"))
      (node (ref "R2") (pin "1") (pinfunction "1_1") (pintype "passive"))
      (node (ref "U2") (pin "12") (pinfunction "VCC_12") (pintype "passive"))
    )
    (net (code "53") (name "3v3") (class "Default")
      (node (ref "C14") (pin "2") (pinfunction "2_2") (pintype "passive"))
      (node (ref "C15") (pin "2") (pinfunction "2_2") (pintype "passive"))
      (node (ref "C4") (pin "2") (pinfunction "2_2") (pintype "passive"))
      (node (ref "C5") (pin "2") (pinfunction "2_2") (pintype "passive"))
      (node (ref "J1") (pin "2") (pinfunction "2_2") (pintype "passive"))
      (node (ref "J2") (pin "1") (pinfunction "1_1") (pintype "passive"))
      (node (ref "J5") (pin "2") (pinfunction "2_2") (pintype "passive"))
      (node (ref "R1") (pin "2") (pinfunction "2_2") (pintype "passive"))
      (node (ref "R10") (pin "2") (pinfunction "2_2") (pintype "passive"))
      (node (ref "R11") (pin "2") (pinfunction "2_2") (pintype "passive"))
      (node (ref "R18") (pin "2") (pinfunction "2_2") (pintype "passive"))
      (node (ref "U1") (pin "3") (pinfunction "3V3_3") (pintype "passive"))
    )
    (net (code "54") (name "3v3_reg") (class "Default")
      (node (ref "C12") (pin "2") (pinfunction "2_2") (pintype "passive"))
      (node (ref "C13") (pin "2") (pinfunction "2_2") (pintype "passive"))
      (node (ref "J5") (pin "1") (pinfunction "1_1") (pintype "passive"))
      (node (ref "U3") (pin "3") (pinfunction "OUT_3") (pintype "power_in"))
    )
    (net (code "55") (name "5v") (class "Default")
      (node (ref "C11") (pin "2") (pinfunction "2_2") (pintype "passive"))
      (node (ref "C9") (pin "2") (pinfunction "2_2") (pintype "passive"))
      (node (ref "J1") (pin "22") (pinfunction "22_22") (pintype "passive"))
      (node (ref "J6") (pin "2") (pinfunction "2_2") (pintype "passive"))
      (node (ref "R2") (pin "2") (pinfunction "2_2") (pintype "passive"))
      (node (ref "U3") (pin "1") (pinfunction "IN_1") (pintype "power_in"))
    )
    (net (code "56") (name "5v_vbus_1") (class "Default")
      (node (ref "C3") (pin "2") (pinfunction "2_2") (pintype "passive"))
      (node (ref "D1") (pin "2") (pinfunction "2_2") (pintype "passive"))
      (node (ref "J3") (pin "A4B9") (pinfunction "VBUS_A4B9_A4B9") (pintype "passive"))
      (node (ref "J3") (pin "B4A9") (pinfunction "VBUS_B4A9_B4A9") (pintype "passive"))
      (node (ref "J6") (pin "1") (pinfunction "1_1") (pintype "passive"))
    )
    (net (code "57") (name "5v_vbus_2") (class "Default")
      (node (ref "C10") (pin "2") (pinfunction "2_2") (pintype "passive"))
      (node (ref "D6") (pin "2") (pinfunction "2_2") (pintype "passive"))
      (node (ref "J4") (pin "A4B9") (pinfunction "VBUS_A4B9_A4B9") (pintype "passive"))
      (node (ref "J4") (pin "B4A9") (pinfunction "VBUS_B4A9_B4A9") (pintype "passive"))
      (node (ref "J6") (pin "3") (pinfunction "3_3") (pintype "passive"))
    )
    (net (code "58") (name "GND") (class "Default")
      (node (ref "C1") (pin "1") (pinfunction "1_1") (pintype "passive"))
      (node (ref "C10") (pin "1") (pinfunction "1_1") (pintype "passive"))
      (node (ref "C11") (pin "1") (pinfunction "1_1") (pintype "passive"))
      (node (ref "C12") (pin "1") (pinfunction "1_1") (pintype "passive"))
      (node (ref "C13") (pin "1") (pinfunction "1_1") (pintype "passive"))
      (node (ref "C14") (pin "1") (pinfunction "1_1") (pintype "passive"))
      (node (ref "C15") (pin "1") (pinfunction "1_1") (pintype "passive"))
      (node (ref "C16") (pin "1") (pinfunction "1_1") (pintype "passive"))
      (node (ref "C2") (pin "1") (pinfunction "1_1") (pintype "passive"))
      (node (ref "C3") (pin "1") (pinfunction "1_1") (pintype "passive"))
      (node (ref "C4") (pin "1") (pinfunction "1_1") (pintype "passive"))
      (node (ref "C5") (pin "1") (pinfunction "1_1") (pintype "passive"))
      (node (ref "C6") (pin "1") (pinfunction "1_1") (pintype "passive"))
      (node (ref "C7") (pin "1") (pinfunction "1_1") (pintype "passive"))
      (node (ref "C8") (pin "1") (pinfunction "1_1") (pintype "passive"))
      (node (ref "C9") (pin "1") (pinfunction "1_1") (pintype "passive"))
      (node (ref "D1") (pin "1") (pinfunction "1_1") (pintype "passive"))
      (node (ref "D2") (pin "1") (pinfunction "1_1") (pintype "passive"))
      (node (ref "D3") (pin "1") (pinfunction "1_1") (pintype "passive"))
      (node (ref "D4") (pin "1") (pinfunction "1_1") (pintype "passive"))
      (node (ref "D6") (pin "1") (pinfunction "1_1") (pintype "passive"))
      (node (ref "D7") (pin "1") (pinfunction "1_1") (pintype "passive"))
      (node (ref "D8") (pin "1") (pinfunction "1_1") (pintype "passive"))
      (node (ref "J1") (pin "1") (pinfunction "1_1") (pintype "passive"))
      (node (ref "J1") (pin "23") (pinfunction "23_23") (pintype "passive"))
      (node (ref "J2") (pin "2") (pinfunction "2_2") (pintype "passive"))
      (node (ref "J2") (pin "24") (pinfunction "24_24") (pintype "passive"))
      (node (ref "J3") (pin "A1B12") (pinfunction "GND_A1B12_A1B12") (pintype "passive"))
      (node (ref "J3") (pin "B1A12") (pinfunction "GND_B1A12_B1A12") (pintype "passive"))
      (node (ref "J3") (pin "S1") (pinfunction "SHIELD_1_S1") (pintype "passive"))
      (node (ref "J3") (pin "S2") (pinfunction "SHIELD_2_S2") (pintype "passive"))
      (node (ref "J3") (pin "S3") (pinfunction "SHIELD_3_S3") (pintype "passive"))
      (node (ref "J3") (pin "S4") (pinfunction "SHIELD_4_S4") (pintype "passive"))
      (node (ref "J4") (pin "A1B12") (pinfunction "GND_A1B12_A1B12") (pintype "passive"))
      (node (ref "J4") (pin "B1A12") (pinfunction "GND_B1A12_B1A12") (pintype "passive"))
      (node (ref "J4") (pin "S1") (pinfunction "SHIELD_1_S1") (pintype "passive"))
      (node (ref "J4") (pin "S2") (pinfunction "SHIELD_2_S2") (pintype "passive"))
      (node (ref "J4") (pin "S3") (pinfunction "SHIELD_3_S3") (pintype "passive"))
      (node (ref "J4") (pin "S4") (pinfunction "SHIELD_4_S4") (pintype "passive"))
      (node (ref "R12") (pin "1") (pinfunction "1_1") (pintype "passive"))
      (node (ref "R13") (pin "1") (pinfunction "1_1") (pintype "passive"))
      (node (ref "R8") (pin "1") (pinfunction "1_1") (pintype "passive"))
      (node (ref "R9") (pin "1") (pinfunction "1_1") (pintype "passive"))
      (node (ref "SW1") (pin "3") (pinfunction "3_3") (pintype "passive"))
      (node (ref "SW2") (pin "3") (pinfunction "3_3") (pintype "passive"))
      (node (ref "U1") (pin "1") (pinfunction "GND_01_1") (pintype "passive"))
      (node (ref "U1") (pin "2") (pinfunction "GND_02_2") (pintype "passive"))
      (node (ref "U1") (pin "42") (pinfunction "GND_42") (pintype "passive"))
      (node (ref "U1") (pin "43") (pinfunction "GND_43") (pintype "passive"))
      (node (ref "U1") (pin "46") (pinfunction "GND_46_46") (pintype "passive"))
      (node (ref "U1") (pin "47") (pinfunction "GND_47_47") (pintype "passive"))
      (node (ref "U1") (pin "48") (pinfunction "GND_48_48") (pintype "passive"))
      (node (ref "U1") (pin "49") (pinfunction "GND_49_49") (pintype "passive"))
      (node (ref "U1") (pin "50") (pinfunction "GND_50_50") (pintype "passive"))
      (node (ref "U1") (pin "51") (pinfunction "GND_51_51") (pintype "passive"))
      (node (ref "U1") (pin "52") (pinfunction "GND_52_52") (pintype "passive"))
      (node (ref "U1") (pin "53") (pinfunction "GND_53_53") (pintype "passive"))
      (node (ref "U1") (pin "54") (pinfunction "GND_54_54") (pintype "passive"))
      (node (ref "U1") (pin "55") (pinfunction "GND_55_55") (pintype "passive"))
      (node (ref "U1") (pin "56") (pinfunction "GND_56_56") (pintype "passive"))
      (node (ref "U1") (pin "57") (pinfunction "GND_57_57") (pintype "passive"))
      (node (ref "U1") (pin "58") (pinfunction "GND_58_58") (pintype "passive"))
      (node (ref "U1") (pin "59") (pinfunction "GND_59_59") (pintype "passive"))
      (node (ref "U1") (pin "60") (pinfunction "GND_60_60") (pintype "passive"))
      (node (ref "U1") (pin "61") (pinfunction "GND_61_61") (pintype "passive"))
      (node (ref "U1") (pin "62") (pinfunction "GND_62_62") (pintype "passive"))
      (node (ref "U1") (pin "63") (pinfunction "GND_63_63") (pintype "passive"))
      (node (ref "U1") (pin "64") (pinfunction "GND_64_64") (pintype "passive"))
      (node (ref "U1") (pin "65") (pinfunction "GND_65_65") (pintype "passive"))
      (node (ref "U1") (pin "66") (pinfunction "GND_66_66") (pintype "passive"))
      (node (ref "U1") (pin "67") (pinfunction "GND_67_67") (pintype "passive"))
      (node (ref "U1") (pin "68") (pinfunction "GND_68_68") (pintype "passive"))
      (node (ref "U1") (pin "69") (pinfunction "GND_69_69") (pintype "passive"))
      (node (ref "U1") (pin "70") (pinfunction "GND_70_70") (pintype "passive"))
      (node (ref "U1") (pin "71") (pinfunction "GND_71_71") (pintype "passive"))
      (node (ref "U1") (pin "72") (pinfunction "GND_72_72") (pintype "passive"))
      (node (ref "U1") (pin "73") (pinfunction "GND_73_73") (pintype "passive"))
      (node (ref "U2") (pin "13") (pinfunction "GND_13") (pintype "passive"))
      (node (ref "U2") (pin "21") (pinfunction "GND_21") (pintype "passive"))
      (node (ref "U2") (pin "3") (pinfunction "GND_3") (pintype "passive"))
      (node (ref "U3") (pin "2") (pinfunction "GND_2") (pintype "power_in"))
      (node (ref "U3") (pin "4") (pinfunction "GND_4") (pintype "power_in"))
    )
    (net (code "59") (name "Net-(D4-Pad2)") (class "Default")
      (node (ref "D4") (pin "2") (pinfunction "2_2") (pintype "passive"))
      (node (ref "R10") (pin "1") (pinfunction "1_1") (pintype "passive"))
    )
    (net (code "60") (name "Net-(D5-Pad2)") (class "Default")
      (node (ref "D5") (pin "2") (pinfunction "2_2") (pintype "passive"))
      (node (ref "R11") (pin "1") (pinfunction "1_1") (pintype "passive"))
    )
    (net (code "61") (name "Net-(J3-CC1)") (class "Default")
      (node (ref "J3") (pin "A5") (pinfunction "CC1_A5") (pintype "passive"))
      (node (ref "R9") (pin "2") (pinfunction "2_2") (pintype "passive"))
    )
    (net (code "62") (name "Net-(J3-CC2)") (class "Default")
      (node (ref "J3") (pin "B5") (pinfunction "CC2_B5") (pintype "passive"))
      (node (ref "R8") (pin "2") (pinfunction "2_2") (pintype "passive"))
    )
    (net (code "63") (name "Net-(J4-CC1)") (class "Default")
      (node (ref "J4") (pin "A5") (pinfunction "CC1_A5") (pintype "passive"))
      (node (ref "R13") (pin "2") (pinfunction "2_2") (pintype "passive"))
    )
    (net (code "64") (name "Net-(J4-CC2)") (class "Default")
      (node (ref "J4") (pin "B5") (pinfunction "CC2_B5") (pintype "passive"))
      (node (ref "R12") (pin "2") (pinfunction "2_2") (pintype "passive"))
    )
    (net (code "65") (name "Net-(Q1-B)") (class "Default")
      (node (ref "Q1") (pin "1") (pinfunction "B_1") (pintype "passive"))
      (node (ref "R3") (pin "2") (pinfunction "2_2") (pintype "passive"))
    )
    (net (code "66") (name "Net-(Q2-B)") (class "Default")
      (node (ref "Q2") (pin "1") (pinfunction "B_1") (pintype "passive"))
      (node (ref "R7") (pin "2") (pinfunction "2_2") (pintype "passive"))
    )
    (net (code "67") (name "Net-(U2-~{RESET})") (class "Default")
      (node (ref "C8") (pin "2") (pinfunction "2_2") (pintype "passive"))
      (node (ref "R6") (pin "1") (pinfunction "1_1") (pintype "passive"))
      (node (ref "U2") (pin "11") (pinfunction "~{RESET}_11") (pintype "passive"))
    )
    (net (code "68") (name "unconnected-(J1-Pad24)") (class "Default")
      (node (ref "J1") (pin "24") (pinfunction "24_24") (pintype "passive+no_connect"))
    )
    (net (code "69") (name "unconnected-(J2-Pad20)") (class "Default")
      (node (ref "J2") (pin "20") (pinfunction "20_20") (pintype "passive+no_connect"))
    )
    (net (code "70") (name "unconnected-(J2-Pad21)") (class "Default")
      (node (ref "J2") (pin "21") (pinfunction "21_21") (pintype "passive+no_connect"))
    )
    (net (code "71") (name "unconnected-(J3-SBU1-PadA8)") (class "Default")
      (node (ref "J3") (pin "A8") (pinfunction "SBU1_A8") (pintype "passive+no_connect"))
    )
    (net (code "72") (name "unconnected-(J3-SBU2-PadB8)") (class "Default")
      (node (ref "J3") (pin "B8") (pinfunction "SBU2_B8") (pintype "passive+no_connect"))
    )
    (net (code "73") (name "unconnected-(J4-SBU1-PadA8)") (class "Default")
      (node (ref "J4") (pin "A8") (pinfunction "SBU1_A8") (pintype "passive"))
    )
    (net (code "74") (name "unconnected-(J4-SBU2-PadB8)") (class "Default")
      (node (ref "J4") (pin "B8") (pinfunction "SBU2_B8") (pintype "passive"))
    )
    (net (code "75") (name "unconnected-(SW1-Pad1)") (class "Default")
      (node (ref "SW1") (pin "1") (pinfunction "1_1") (pintype "passive+no_connect"))
    )
    (net (code "76") (name "unconnected-(SW1-Pad4)") (class "Default")
      (node (ref "SW1") (pin "4") (pinfunction "4_4") (pintype "passive+no_connect"))
    )
    (net (code "77") (name "unconnected-(SW2-Pad1)") (class "Default")
      (node (ref "SW2") (pin "1") (pinfunction "1_1") (pintype "passive+no_connect"))
    )
    (net (code "78") (name "unconnected-(SW2-Pad4)") (class "Default")
      (node (ref "SW2") (pin "4") (pinfunction "4_4") (pintype "passive+no_connect"))
    )
    (net (code "79") (name "unconnected-(U2-CBUS0-Pad15)") (class "Default")
      (node (ref "U2") (pin "15") (pinfunction "CBUS0_15") (pintype "passive+no_connect"))
    )
    (net (code "80") (name "unconnected-(U2-CBUS1-Pad14)") (class "Default")
      (node (ref "U2") (pin "14") (pinfunction "CBUS1_14") (pintype "passive+no_connect"))
    )
    (net (code "81") (name "unconnected-(U2-CBUS2-Pad7)") (class "Default")
      (node (ref "U2") (pin "7") (pinfunction "CBUS2_7") (pintype "passive+no_connect"))
    )
    (net (code "82") (name "unconnected-(U2-CBUS3-Pad16)") (class "Default")
      (node (ref "U2") (pin "16") (pinfunction "CBUS3_16") (pintype "passive+no_connect"))
    )
    (net (code "83") (name "unconnected-(U2-~{CTS}-Pad6)") (class "Default")
      (node (ref "U2") (pin "6") (pinfunction "~{CTS}_6") (pintype "passive+no_connect"))
    )
    (net (code "84") (name "unconnected-(U2-~{DCD}-Pad5)") (class "Default")
      (node (ref "U2") (pin "5") (pinfunction "~{DCD}_5") (pintype "passive+no_connect"))
    )
    (net (code "85") (name "unconnected-(U2-~{DSR}-Pad4)") (class "Default")
      (node (ref "U2") (pin "4") (pinfunction "~{DSR}_4") (pintype "passive+no_connect"))
    )
    (net (code "86") (name "unconnected-(U2-~{RI}-Pad2)") (class "Default")
      (node (ref "U2") (pin "2") (pinfunction "~{RI}_2") (pintype "passive+no_connect"))
    )
  )
)
